# calkabot1.net
KiCad netlist of a schematic drawn in EAGLE
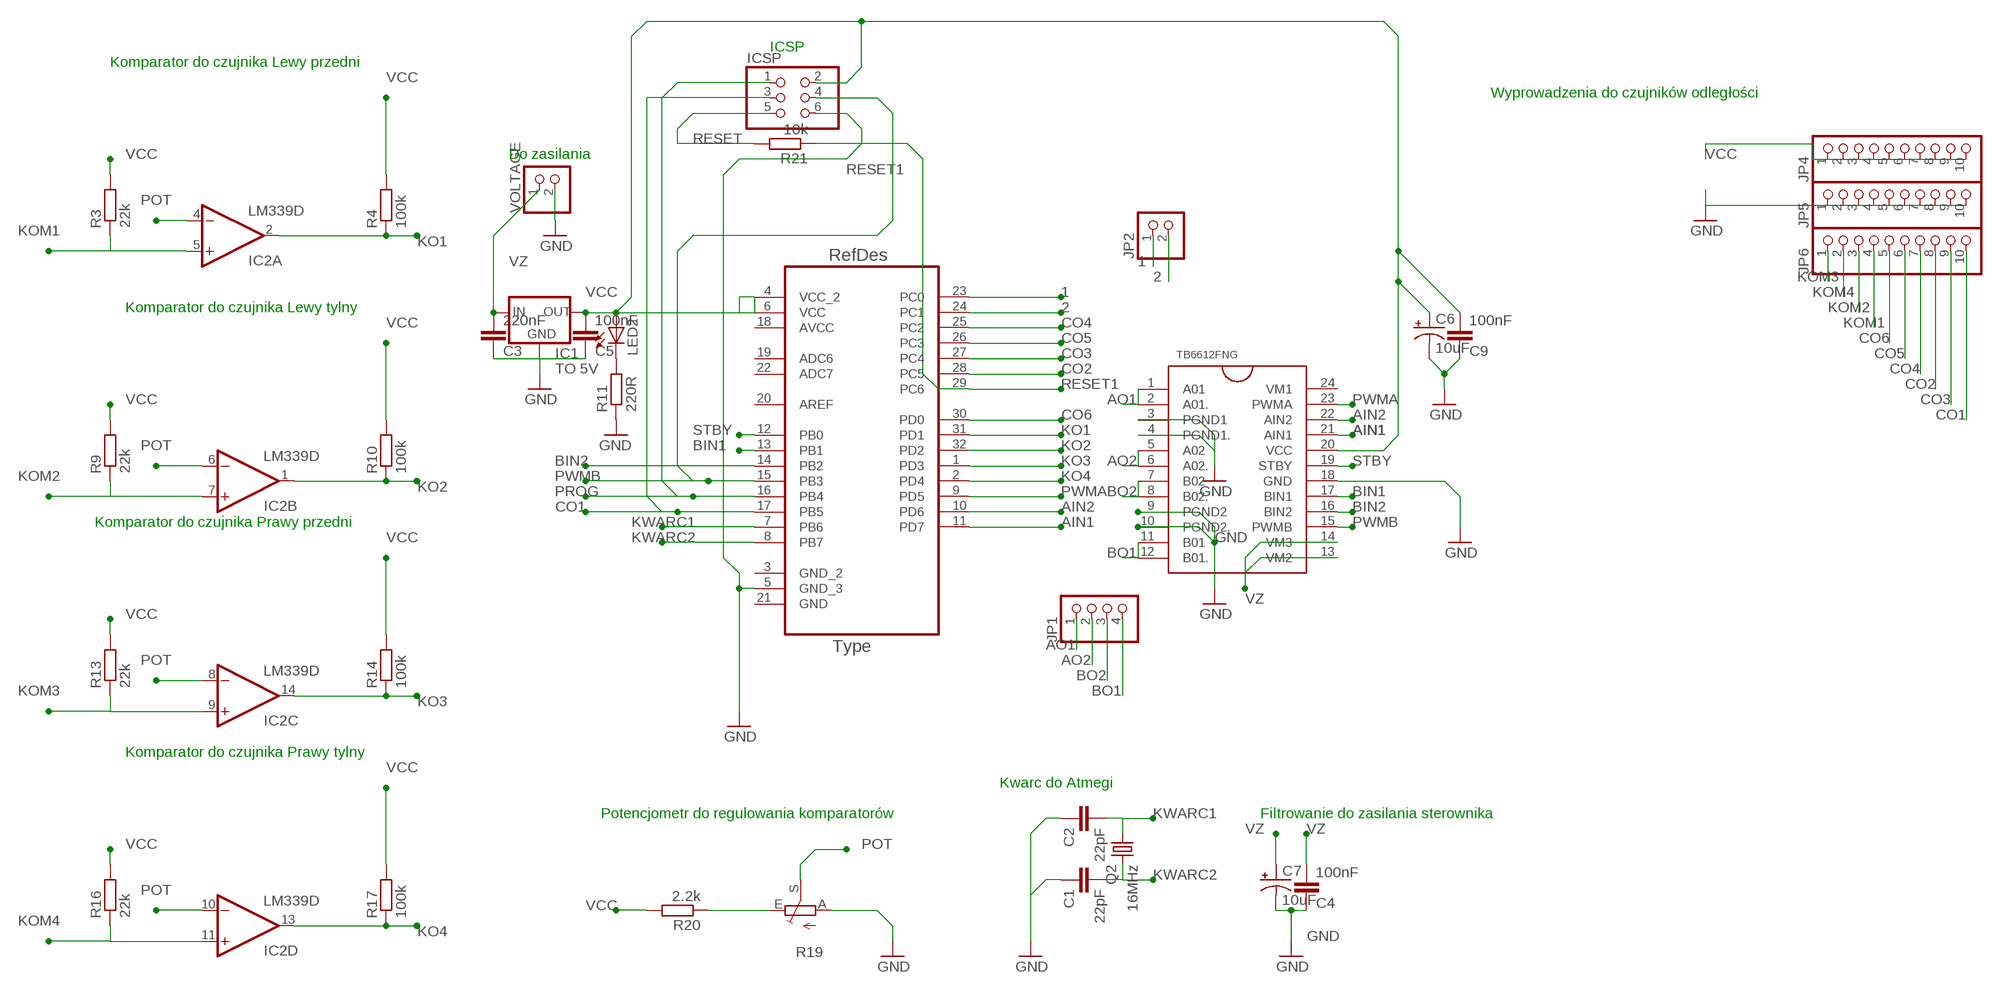
[diagram p0: schematic, sheet 1]

(export (version "E")
  (design (tool "Eeschema 10.0.6"))
  (components
    (comp (ref "C1")
      (value "22pF")
      (footprint "eagle-import:C0805")
      (fields (field (name "SPICEPREFIX") "C"))
      (libsource (lib "eagle-import") (part "C-EUC0805"))
    )
    (comp (ref "C2")
      (value "22pF")
      (footprint "eagle-import:C0805")
      (libsource (lib "eagle-import") (part "C-EUC0805"))
    )
    (comp (ref "C3")
      (value "220nF")
      (footprint "eagle-import:C0805")
      (fields (field (name "SPICEPREFIX") "C"))
      (libsource (lib "eagle-import") (part "C-EUC0805"))
    )
    (comp (ref "C4")
      (value "100nF")
      (footprint "eagle-import:C0805")
      (fields (field (name "SPICEPREFIX") "C"))
      (libsource (lib "eagle-import") (part "C-EUC0805"))
    )
    (comp (ref "C5")
      (value "100nF")
      (footprint "eagle-import:C0805")
      (fields (field (name "SPICEPREFIX") "C"))
      (libsource (lib "eagle-import") (part "C-EUC0805"))
    )
    (comp (ref "C6")
      (value "10uF")
      (footprint "eagle-import:PANASONIC_C")
      (libsource (lib "eagle-import") (part "22UF-POLAR-PANASONIC_C-35V-20%"))
    )
    (comp (ref "C7")
      (value "10uF")
      (footprint "eagle-import:PANASONIC_C")
      (libsource (lib "eagle-import") (part "22UF-POLAR-PANASONIC_C-35V-20%"))
    )
    (comp (ref "C9")
      (value "100nF")
      (footprint "eagle-import:C0805")
      (fields (field (name "SPICEPREFIX") "C"))
      (libsource (lib "eagle-import") (part "C-EUC0805"))
    )
    (comp (ref "IC1")
      (value "TO 5V")
      (footprint "eagle-import:TO220V")
      (libsource (lib "eagle-import") (part "LM1117T--V5.0"))
    )
    (comp (ref "IC2")
      (value "LM339D")
      (footprint "eagle-import:SO14")
      (libsource (lib "eagle-import") (part "LM339D"))
    )
    (comp (ref "ICSP")
      (value "PINHD-2X3")
      (footprint "eagle-import:2X03")
      (libsource (lib "eagle-import") (part "PINHD-2X3"))
    )
    (comp (ref "JP1")
      (value "PINHD-1X4")
      (footprint "eagle-import:1X04")
      (libsource (lib "eagle-import") (part "PINHD-1X4"))
    )
    (comp (ref "JP2")
      (value "PINHD-1X2")
      (footprint "eagle-import:1X02")
      (libsource (lib "eagle-import") (part "PINHD-1X2"))
    )
    (comp (ref "JP4")
      (value "PINHD-1X10")
      (footprint "eagle-import:1X10")
      (libsource (lib "eagle-import") (part "PINHD-1X10"))
    )
    (comp (ref "JP5")
      (value "PINHD-1X10")
      (footprint "eagle-import:1X10")
      (libsource (lib "eagle-import") (part "PINHD-1X10"))
    )
    (comp (ref "JP6")
      (value "PINHD-1X10")
      (footprint "eagle-import:1X10")
      (libsource (lib "eagle-import") (part "PINHD-1X10"))
    )
    (comp (ref "LED2")
      (value "LEDCHIPLED_0805")
      (footprint "eagle-import:CHIPLED_0805")
      (libsource (lib "eagle-import") (part "LEDCHIPLED_0805"))
    )
    (comp (ref "Q2")
      (value "16MHz")
      (footprint "eagle-import:CSM-7X-DU")
      (libsource (lib "eagle-import") (part "CSM-7X-DU"))
    )
    (comp (ref "R3")
      (value "22k")
      (footprint "eagle-import:M0805")
      (libsource (lib "eagle-import") (part "R-EU_M0805"))
    )
    (comp (ref "R4")
      (value "100k")
      (footprint "eagle-import:M0805")
      (libsource (lib "eagle-import") (part "R-EU_M0805"))
    )
    (comp (ref "R9")
      (value "22k")
      (footprint "eagle-import:M0805")
      (libsource (lib "eagle-import") (part "R-EU_M0805"))
    )
    (comp (ref "R10")
      (value "100k")
      (footprint "eagle-import:M0805")
      (libsource (lib "eagle-import") (part "R-EU_M0805"))
    )
    (comp (ref "R11")
      (value "220R")
      (footprint "eagle-import:M0805")
      (libsource (lib "eagle-import") (part "R-EU_M0805"))
    )
    (comp (ref "R13")
      (value "22k")
      (footprint "eagle-import:M0805")
      (libsource (lib "eagle-import") (part "R-EU_M0805"))
    )
    (comp (ref "R14")
      (value "100k")
      (footprint "eagle-import:M0805")
      (libsource (lib "eagle-import") (part "R-EU_M0805"))
    )
    (comp (ref "R16")
      (value "22k")
      (footprint "eagle-import:M0805")
      (libsource (lib "eagle-import") (part "R-EU_M0805"))
    )
    (comp (ref "R17")
      (value "100k")
      (footprint "eagle-import:M0805")
      (libsource (lib "eagle-import") (part "R-EU_M0805"))
    )
    (comp (ref "R19")
      (value "TRIM_EU-B25P")
      (footprint "eagle-import:B25P")
      (libsource (lib "eagle-import") (part "TRIM_EU-B25P"))
    )
    (comp (ref "R20")
      (value "2.2k")
      (footprint "eagle-import:M0805")
      (libsource (lib "eagle-import") (part "R-EU_M0805"))
    )
    (comp (ref "R21")
      (value "10k")
      (footprint "eagle-import:M0805")
      (libsource (lib "eagle-import") (part "R-EU_M0805"))
    )
    (comp (ref "U$1")
      (value "TB6612FNG")
      (footprint "eagle-import:SSOP24")
      (libsource (lib "eagle-import") (part "TB6612FNG"))
    )
    (comp (ref "U1")
      (value "ATMEGA328P-AU")
      (footprint "eagle-import:QFP80P900X900X120-32N")
      (libsource (lib "eagle-import") (part "ATMEGA328P-AU"))
    )
    (comp (ref "VOLTAGE")
      (value "PINHD-1X2")
      (footprint "eagle-import:1X02")
      (libsource (lib "eagle-import") (part "PINHD-1X2"))
    )
  )
  (nets
    (net (code "1") (name "/1") (class "Default")
      (node (ref "JP2") (pin "1") (pinfunction "1_1") (pintype "passive"))
      (node (ref "U1") (pin "23") (pinfunction "PC0_23") (pintype "bidirectional"))
    )
    (net (code "2") (name "/2") (class "Default")
      (node (ref "JP2") (pin "2") (pinfunction "2_2") (pintype "passive"))
      (node (ref "U1") (pin "24") (pinfunction "PC1_24") (pintype "bidirectional"))
    )
    (net (code "3") (name "/AIN1") (class "Default")
      (node (ref "U$1") (pin "21") (pinfunction "AIN1_21") (pintype "bidirectional"))
      (node (ref "U1") (pin "11") (pinfunction "PD7_11") (pintype "bidirectional"))
    )
    (net (code "4") (name "/AIN2") (class "Default")
      (node (ref "U$1") (pin "22") (pinfunction "AIN2_22") (pintype "bidirectional"))
      (node (ref "U1") (pin "10") (pinfunction "PD6_10") (pintype "bidirectional"))
    )
    (net (code "5") (name "/AO1") (class "Default")
      (node (ref "JP1") (pin "1") (pinfunction "1_1") (pintype "passive"))
      (node (ref "U$1") (pin "1") (pinfunction "A01_1") (pintype "bidirectional"))
      (node (ref "U$1") (pin "2") (pinfunction "A01._2") (pintype "bidirectional"))
    )
    (net (code "6") (name "/AO2") (class "Default")
      (node (ref "JP1") (pin "2") (pinfunction "2_2") (pintype "passive"))
      (node (ref "U$1") (pin "5") (pinfunction "A02_5") (pintype "bidirectional"))
      (node (ref "U$1") (pin "6") (pinfunction "A02._6") (pintype "bidirectional"))
    )
    (net (code "7") (name "/AVCC") (class "Default")
      (node (ref "U1") (pin "18") (pinfunction "AVCC_18") (pintype "power_in"))
    )
    (net (code "8") (name "/BIN1") (class "Default")
      (node (ref "U$1") (pin "17") (pinfunction "BIN1_17") (pintype "bidirectional"))
      (node (ref "U1") (pin "13") (pinfunction "PB1_13") (pintype "bidirectional"))
    )
    (net (code "9") (name "/BIN2") (class "Default")
      (node (ref "U$1") (pin "16") (pinfunction "BIN2_16") (pintype "bidirectional"))
      (node (ref "U1") (pin "14") (pinfunction "PB2_14") (pintype "bidirectional"))
    )
    (net (code "10") (name "/BO1") (class "Default")
      (node (ref "JP1") (pin "4") (pinfunction "4_4") (pintype "passive"))
      (node (ref "U$1") (pin "11") (pinfunction "B01_11") (pintype "bidirectional"))
      (node (ref "U$1") (pin "12") (pinfunction "B01._12") (pintype "bidirectional"))
    )
    (net (code "11") (name "/BO2") (class "Default")
      (node (ref "JP1") (pin "3") (pinfunction "3_3") (pintype "passive"))
      (node (ref "U$1") (pin "7") (pinfunction "B02_7") (pintype "bidirectional"))
      (node (ref "U$1") (pin "8") (pinfunction "B02._8") (pintype "bidirectional"))
    )
    (net (code "12") (name "/CO1") (class "Default")
      (node (ref "ICSP") (pin "3") (pinfunction "3_3") (pintype "passive"))
      (node (ref "JP6") (pin "10") (pinfunction "10_10") (pintype "passive"))
      (node (ref "U1") (pin "17") (pinfunction "PB5_17") (pintype "bidirectional"))
    )
    (net (code "13") (name "/CO2") (class "Default")
      (node (ref "JP6") (pin "8") (pinfunction "8_8") (pintype "passive"))
      (node (ref "U1") (pin "28") (pinfunction "PC5_28") (pintype "bidirectional"))
    )
    (net (code "14") (name "/CO3") (class "Default")
      (node (ref "JP6") (pin "9") (pinfunction "9_9") (pintype "passive"))
      (node (ref "U1") (pin "27") (pinfunction "PC4_27") (pintype "bidirectional"))
    )
    (net (code "15") (name "/CO4") (class "Default")
      (node (ref "JP6") (pin "7") (pinfunction "7_7") (pintype "passive"))
      (node (ref "U1") (pin "25") (pinfunction "PC2_25") (pintype "bidirectional"))
    )
    (net (code "16") (name "/CO5") (class "Default")
      (node (ref "JP6") (pin "6") (pinfunction "6_6") (pintype "passive"))
      (node (ref "U1") (pin "26") (pinfunction "PC3_26") (pintype "bidirectional"))
    )
    (net (code "17") (name "/CO6") (class "Default")
      (node (ref "JP6") (pin "5") (pinfunction "5_5") (pintype "passive"))
      (node (ref "U1") (pin "30") (pinfunction "PD0_30") (pintype "bidirectional"))
    )
    (net (code "18") (name "/KO1") (class "Default")
      (node (ref "IC2") (pin "2") (pinfunction "OUT_2") (pintype "open_collector"))
      (node (ref "R4") (pin "1") (pinfunction "1_1") (pintype "passive"))
      (node (ref "U1") (pin "31") (pinfunction "PD1_31") (pintype "bidirectional"))
    )
    (net (code "19") (name "/KO2") (class "Default")
      (node (ref "IC2") (pin "1") (pinfunction "OUT_1") (pintype "open_collector"))
      (node (ref "R10") (pin "1") (pinfunction "1_1") (pintype "passive"))
      (node (ref "U1") (pin "32") (pinfunction "PD2_32") (pintype "bidirectional"))
    )
    (net (code "20") (name "/KO3") (class "Default")
      (node (ref "IC2") (pin "14") (pinfunction "OUT_14") (pintype "open_collector"))
      (node (ref "R14") (pin "1") (pinfunction "1_1") (pintype "passive"))
      (node (ref "U1") (pin "1") (pinfunction "PD3_1") (pintype "bidirectional"))
    )
    (net (code "21") (name "/KO4") (class "Default")
      (node (ref "IC2") (pin "13") (pinfunction "OUT_13") (pintype "open_collector"))
      (node (ref "R17") (pin "1") (pinfunction "1_1") (pintype "passive"))
      (node (ref "U1") (pin "2") (pinfunction "PD4_2") (pintype "bidirectional"))
    )
    (net (code "22") (name "/KOM1") (class "Default")
      (node (ref "IC2") (pin "5") (pinfunction "+IN_5") (pintype "input"))
      (node (ref "JP6") (pin "4") (pinfunction "4_4") (pintype "passive"))
      (node (ref "R3") (pin "1") (pinfunction "1_1") (pintype "passive"))
    )
    (net (code "23") (name "/KOM2") (class "Default")
      (node (ref "IC2") (pin "7") (pinfunction "+IN_7") (pintype "input"))
      (node (ref "JP6") (pin "3") (pinfunction "3_3") (pintype "passive"))
      (node (ref "R9") (pin "1") (pinfunction "1_1") (pintype "passive"))
    )
    (net (code "24") (name "/KOM3") (class "Default")
      (node (ref "IC2") (pin "9") (pinfunction "+IN_9") (pintype "input"))
      (node (ref "JP6") (pin "1") (pinfunction "1_1") (pintype "passive"))
      (node (ref "R13") (pin "1") (pinfunction "1_1") (pintype "passive"))
    )
    (net (code "25") (name "/KOM4") (class "Default")
      (node (ref "IC2") (pin "11") (pinfunction "+IN_11") (pintype "input"))
      (node (ref "JP6") (pin "2") (pinfunction "2_2") (pintype "passive"))
      (node (ref "R16") (pin "1") (pinfunction "1_1") (pintype "passive"))
    )
    (net (code "26") (name "/KWARC1") (class "Default")
      (node (ref "C2") (pin "2") (pinfunction "2_2") (pintype "passive"))
      (node (ref "Q2") (pin "1") (pinfunction "1_1") (pintype "passive"))
      (node (ref "U1") (pin "7") (pinfunction "PB6_7") (pintype "bidirectional"))
    )
    (net (code "27") (name "/KWARC2") (class "Default")
      (node (ref "C1") (pin "2") (pinfunction "2_2") (pintype "passive"))
      (node (ref "Q2") (pin "2") (pinfunction "2_2") (pintype "passive"))
      (node (ref "U1") (pin "8") (pinfunction "PB7_8") (pintype "bidirectional"))
    )
    (net (code "28") (name "/POT") (class "Default")
      (node (ref "IC2") (pin "10") (pinfunction "-IN_10") (pintype "input"))
      (node (ref "IC2") (pin "4") (pinfunction "-IN_4") (pintype "input"))
      (node (ref "IC2") (pin "6") (pinfunction "-IN_6") (pintype "input"))
      (node (ref "IC2") (pin "8") (pinfunction "-IN_8") (pintype "input"))
      (node (ref "R19") (pin "S") (pinfunction "S_S") (pintype "passive"))
    )
    (net (code "29") (name "/PROG") (class "Default")
      (node (ref "ICSP") (pin "1") (pinfunction "1_1") (pintype "passive"))
      (node (ref "U1") (pin "16") (pinfunction "PB4_16") (pintype "bidirectional"))
    )
    (net (code "30") (name "/PWMA") (class "Default")
      (node (ref "U$1") (pin "23") (pinfunction "PWMA_23") (pintype "bidirectional"))
      (node (ref "U1") (pin "9") (pinfunction "PD5_9") (pintype "bidirectional"))
    )
    (net (code "31") (name "/PWMB") (class "Default")
      (node (ref "ICSP") (pin "4") (pinfunction "4_4") (pintype "passive"))
      (node (ref "U$1") (pin "15") (pinfunction "PWMB_15") (pintype "bidirectional"))
      (node (ref "U1") (pin "15") (pinfunction "PB3_15") (pintype "bidirectional"))
    )
    (net (code "32") (name "/RESET") (class "Default")
      (node (ref "ICSP") (pin "5") (pinfunction "5_5") (pintype "passive"))
      (node (ref "R21") (pin "2") (pinfunction "2_2") (pintype "passive"))
    )
    (net (code "33") (name "/RESET1") (class "Default")
      (node (ref "R21") (pin "1") (pinfunction "1_1") (pintype "passive"))
      (node (ref "U1") (pin "29") (pinfunction "PC6_29") (pintype "bidirectional"))
    )
    (net (code "34") (name "/STBY") (class "Default")
      (node (ref "U$1") (pin "19") (pinfunction "STBY_19") (pintype "bidirectional"))
      (node (ref "U1") (pin "12") (pinfunction "PB0_12") (pintype "bidirectional"))
    )
    (net (code "35") (name "/VCC") (class "Default")
      (node (ref "C5") (pin "2") (pinfunction "2_2") (pintype "passive"))
      (node (ref "C6") (pin "+") (pinfunction "+_+") (pintype "passive"))
      (node (ref "C9") (pin "2") (pinfunction "2_2") (pintype "passive"))
      (node (ref "IC1") (pin "2") (pinfunction "OUT_2") (pintype "passive"))
      (node (ref "ICSP") (pin "2") (pinfunction "2_2") (pintype "passive"))
      (node (ref "JP4") (pin "10") (pinfunction "10_10") (pintype "passive"))
      (node (ref "LED2") (pin "A") (pinfunction "A_A") (pintype "passive"))
      (node (ref "R10") (pin "2") (pinfunction "2_2") (pintype "passive"))
      (node (ref "R13") (pin "2") (pinfunction "2_2") (pintype "passive"))
      (node (ref "R14") (pin "2") (pinfunction "2_2") (pintype "passive"))
      (node (ref "R16") (pin "2") (pinfunction "2_2") (pintype "passive"))
      (node (ref "R17") (pin "2") (pinfunction "2_2") (pintype "passive"))
      (node (ref "R20") (pin "2") (pinfunction "2_2") (pintype "passive"))
      (node (ref "R3") (pin "2") (pinfunction "2_2") (pintype "passive"))
      (node (ref "R4") (pin "2") (pinfunction "2_2") (pintype "passive"))
      (node (ref "R9") (pin "2") (pinfunction "2_2") (pintype "passive"))
      (node (ref "U$1") (pin "20") (pinfunction "VCC_20") (pintype "bidirectional"))
      (node (ref "U1") (pin "4") (pinfunction "VCC_2_4") (pintype "power_in"))
      (node (ref "U1") (pin "6") (pinfunction "VCC_6") (pintype "power_in"))
    )
    (net (code "36") (name "/VZ") (class "Default")
      (node (ref "C3") (pin "2") (pinfunction "2_2") (pintype "passive"))
      (node (ref "C4") (pin "2") (pinfunction "2_2") (pintype "passive"))
      (node (ref "C7") (pin "+") (pinfunction "+_+") (pintype "passive"))
      (node (ref "IC1") (pin "3") (pinfunction "IN_3") (pintype "input"))
      (node (ref "U$1") (pin "13") (pinfunction "VM2_13") (pintype "bidirectional"))
      (node (ref "U$1") (pin "14") (pinfunction "VM3_14") (pintype "bidirectional"))
      (node (ref "VOLTAGE") (pin "1") (pinfunction "1_1") (pintype "passive"))
    )
    (net (code "37") (name "GND") (class "Default")
      (node (ref "C1") (pin "1") (pinfunction "1_1") (pintype "passive"))
      (node (ref "C2") (pin "1") (pinfunction "1_1") (pintype "passive"))
      (node (ref "C3") (pin "1") (pinfunction "1_1") (pintype "passive"))
      (node (ref "C4") (pin "1") (pinfunction "1_1") (pintype "passive"))
      (node (ref "C5") (pin "1") (pinfunction "1_1") (pintype "passive"))
      (node (ref "C6") (pin "-") (pinfunction "-_-") (pintype "passive"))
      (node (ref "C7") (pin "-") (pinfunction "-_-") (pintype "passive"))
      (node (ref "C9") (pin "1") (pinfunction "1_1") (pintype "passive"))
      (node (ref "IC1") (pin "1") (pinfunction "GND_1") (pintype "input"))
      (node (ref "ICSP") (pin "6") (pinfunction "6_6") (pintype "passive"))
      (node (ref "JP5") (pin "10") (pinfunction "10_10") (pintype "passive"))
      (node (ref "R11") (pin "1") (pinfunction "1_1") (pintype "passive"))
      (node (ref "R19") (pin "A") (pinfunction "A_A") (pintype "passive"))
      (node (ref "U$1") (pin "10") (pinfunction "PGND2._10") (pintype "bidirectional"))
      (node (ref "U$1") (pin "18") (pinfunction "GND_18") (pintype "bidirectional"))
      (node (ref "U$1") (pin "3") (pinfunction "PGND1_3") (pintype "bidirectional"))
      (node (ref "U$1") (pin "4") (pinfunction "PGND1._4") (pintype "bidirectional"))
      (node (ref "U$1") (pin "9") (pinfunction "PGND2_9") (pintype "bidirectional"))
      (node (ref "U1") (pin "5") (pinfunction "GND_3_5") (pintype "passive"))
      (node (ref "VOLTAGE") (pin "2") (pinfunction "2_2") (pintype "passive"))
    )
    (net (code "38") (name "Net-(LED2-PadC)") (class "Default")
      (node (ref "LED2") (pin "C") (pinfunction "C_C") (pintype "passive"))
      (node (ref "R11") (pin "2") (pinfunction "2_2") (pintype "passive"))
    )
    (net (code "39") (name "Net-(R19-PadE)") (class "Default")
      (node (ref "R19") (pin "E") (pinfunction "E_E") (pintype "passive"))
      (node (ref "R20") (pin "1") (pinfunction "1_1") (pintype "passive"))
    )
    (net (code "40") (name "unconnected-(JP4-Pad1)") (class "Default")
      (node (ref "JP4") (pin "1") (pinfunction "1_1") (pintype "passive"))
    )
    (net (code "41") (name "unconnected-(JP4-Pad2)") (class "Default")
      (node (ref "JP4") (pin "2") (pinfunction "2_2") (pintype "passive"))
    )
    (net (code "42") (name "unconnected-(JP4-Pad3)") (class "Default")
      (node (ref "JP4") (pin "3") (pinfunction "3_3") (pintype "passive"))
    )
    (net (code "43") (name "unconnected-(JP4-Pad4)") (class "Default")
      (node (ref "JP4") (pin "4") (pinfunction "4_4") (pintype "passive"))
    )
    (net (code "44") (name "unconnected-(JP4-Pad5)") (class "Default")
      (node (ref "JP4") (pin "5") (pinfunction "5_5") (pintype "passive"))
    )
    (net (code "45") (name "unconnected-(JP4-Pad6)") (class "Default")
      (node (ref "JP4") (pin "6") (pinfunction "6_6") (pintype "passive"))
    )
    (net (code "46") (name "unconnected-(JP4-Pad7)") (class "Default")
      (node (ref "JP4") (pin "7") (pinfunction "7_7") (pintype "passive"))
    )
    (net (code "47") (name "unconnected-(JP4-Pad8)") (class "Default")
      (node (ref "JP4") (pin "8") (pinfunction "8_8") (pintype "passive"))
    )
    (net (code "48") (name "unconnected-(JP4-Pad9)") (class "Default")
      (node (ref "JP4") (pin "9") (pinfunction "9_9") (pintype "passive"))
    )
    (net (code "49") (name "unconnected-(JP5-Pad1)") (class "Default")
      (node (ref "JP5") (pin "1") (pinfunction "1_1") (pintype "passive"))
    )
    (net (code "50") (name "unconnected-(JP5-Pad2)") (class "Default")
      (node (ref "JP5") (pin "2") (pinfunction "2_2") (pintype "passive"))
    )
    (net (code "51") (name "unconnected-(JP5-Pad3)") (class "Default")
      (node (ref "JP5") (pin "3") (pinfunction "3_3") (pintype "passive"))
    )
    (net (code "52") (name "unconnected-(JP5-Pad4)") (class "Default")
      (node (ref "JP5") (pin "4") (pinfunction "4_4") (pintype "passive"))
    )
    (net (code "53") (name "unconnected-(JP5-Pad5)") (class "Default")
      (node (ref "JP5") (pin "5") (pinfunction "5_5") (pintype "passive"))
    )
    (net (code "54") (name "unconnected-(JP5-Pad6)") (class "Default")
      (node (ref "JP5") (pin "6") (pinfunction "6_6") (pintype "passive"))
    )
    (net (code "55") (name "unconnected-(JP5-Pad7)") (class "Default")
      (node (ref "JP5") (pin "7") (pinfunction "7_7") (pintype "passive"))
    )
    (net (code "56") (name "unconnected-(JP5-Pad8)") (class "Default")
      (node (ref "JP5") (pin "8") (pinfunction "8_8") (pintype "passive"))
    )
    (net (code "57") (name "unconnected-(JP5-Pad9)") (class "Default")
      (node (ref "JP5") (pin "9") (pinfunction "9_9") (pintype "passive"))
    )
    (net (code "58") (name "unconnected-(U$1-VM1-Pad24)") (class "Default")
      (node (ref "U$1") (pin "24") (pinfunction "VM1_24") (pintype "bidirectional"))
    )
    (net (code "59") (name "unconnected-(U1-ADC6-Pad19)") (class "Default")
      (node (ref "U1") (pin "19") (pinfunction "ADC6_19") (pintype "input"))
    )
    (net (code "60") (name "unconnected-(U1-ADC7-Pad22)") (class "Default")
      (node (ref "U1") (pin "22") (pinfunction "ADC7_22") (pintype "input"))
    )
    (net (code "61") (name "unconnected-(U1-AREF-Pad20)") (class "Default")
      (node (ref "U1") (pin "20") (pinfunction "AREF_20") (pintype "input"))
    )
    (net (code "62") (name "unconnected-(U1-GND-Pad21)") (class "Default")
      (node (ref "U1") (pin "21") (pinfunction "GND_21") (pintype "passive"))
    )
    (net (code "63") (name "unconnected-(U1-GND_2-Pad3)") (class "Default")
      (node (ref "U1") (pin "3") (pinfunction "GND_2_3") (pintype "passive"))
    )
  )
)
